# CONNECTIVITY.net
KiCad netlist of a schematic drawn in Altium Designer
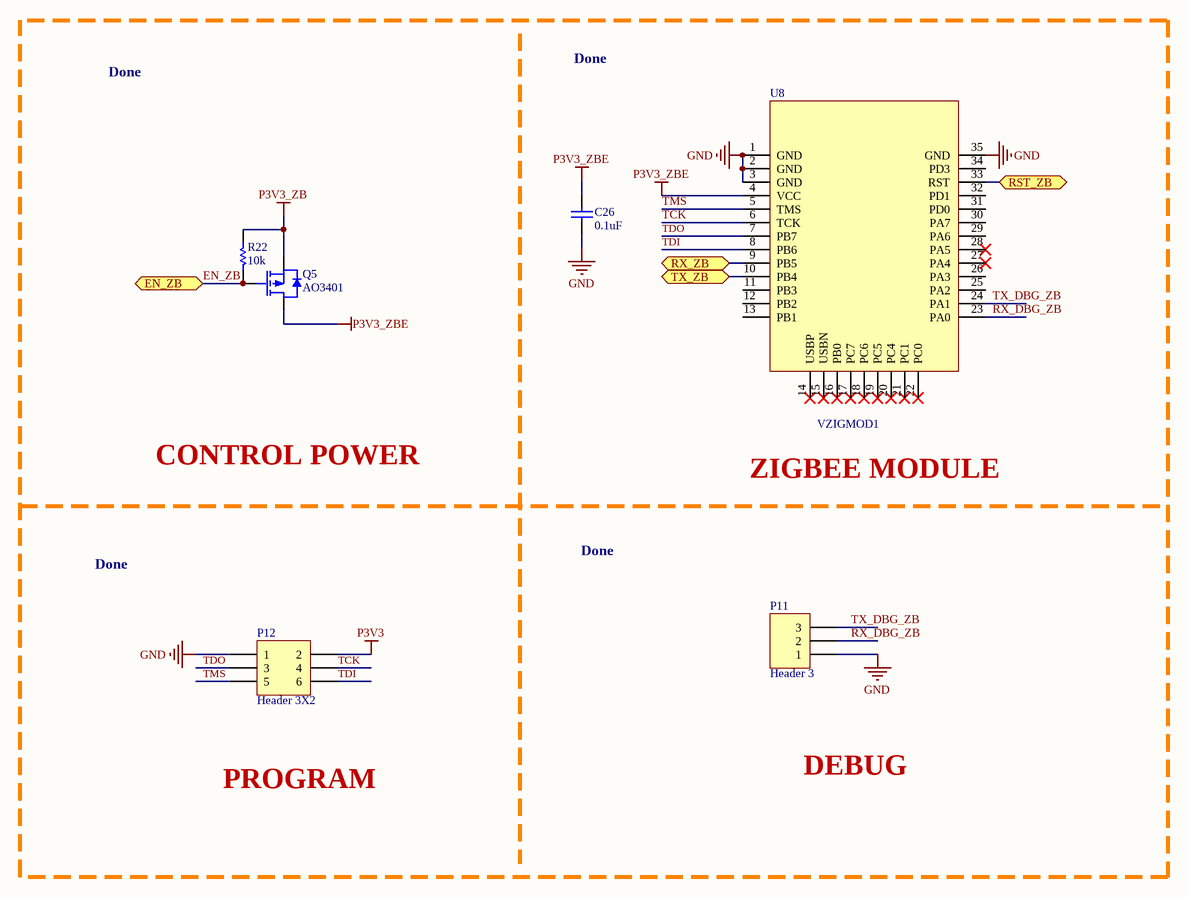
[diagram p0: CONNECTIVITY.SchDoc]

(export (version "E")
  (design (tool "Eeschema 10.0.6"))
  (components
    (comp (ref "C26")
      (value "0.1uF")
      (footprint "C0402M")
      (description "CAP CER 0.1UF 16V X7R 0402")
      (fields
        (field (name "MANUFACTURER") "Samsung Electro-Mechanics")
        (field (name "MANUFACTURER PART NUMBER") "CL05B104KO5NNNC")
      )
      (libsource (lib "BinhLib") (part "CAP0.1u0402"))
    )
    (comp (ref "P11")
      (value "Header 3")
      (footprint "HDR1X3")
      (description "Header, 3-Pin")
      (fields (field (name "PUBLISHER") "Altium Limited"))
      (libsource (lib "BinhLib") (part "Header 3"))
    )
    (comp (ref "P12")
      (value "Header 3X2")
      (footprint "HDR2X3")
      (description "Header, 3-Pin, Dual row")
      (fields (field (name "PUBLISHER") "Altium Limited"))
      (libsource (lib "BinhLib") (part "Header 3X2"))
    )
    (comp (ref "Q5")
      (value "AO3401")
      (footprint "SOT23-3N")
      (description "P-Channel MOSFET")
      (libsource (lib "BinhLib") (part "MOSFET-P1"))
    )
    (comp (ref "R22")
      (value "10k")
      (footprint "R0603M")
      (description "RES SMD 10K OHM 1% 1/10W 0603")
      (fields
        (field (name "MANUFACTURER") "Panasonic Electronic Components")
        (field (name "MANUFACTURER PART NUMBER") "ERJ-3EKF1002V")
      )
      (libsource (lib "BinhLib") (part "RES10k0603"))
    )
    (comp (ref "U8")
      (value "VZIGMOD1")
      (footprint "VZIGMOD2")
      (description "VNPT ZIGBEE MODULE V1 - No-PA")
      (fields (field (name "MANUFACTURER") "VNPT-Technology") (field (name "UTILIZED IC / PART") "CC2538"))
      (libsource (lib "SensorNode") (part "VZIGMOD2"))
    )
  )
  (nets
    (net (code "1") (name "/EN_ZB") (class "Default")
      (node (ref "Q5") (pin "1") (pinfunction "G_1") (pintype "passive"))
      (node (ref "R22") (pin "1") (pinfunction "1_1") (pintype "passive"))
    )
    (net (code "2") (name "/RST_ZB") (class "Default")
      (node (ref "U8") (pin "33") (pinfunction "RST_33") (pintype "passive"))
    )
    (net (code "3") (name "/RX_DBG_ZB") (class "Default")
      (node (ref "P11") (pin "2") (pinfunction "2_2") (pintype "passive"))
      (node (ref "U8") (pin "23") (pinfunction "PA0_23") (pintype "passive"))
    )
    (net (code "4") (name "/RX_ZB") (class "Default")
      (node (ref "U8") (pin "9") (pinfunction "PB5_9") (pintype "passive"))
    )
    (net (code "5") (name "/TCK") (class "Default")
      (node (ref "P12") (pin "4") (pinfunction "4_4") (pintype "passive"))
      (node (ref "U8") (pin "6") (pinfunction "TCK_6") (pintype "passive"))
    )
    (net (code "6") (name "/TDI") (class "Default")
      (node (ref "P12") (pin "6") (pinfunction "6_6") (pintype "passive"))
      (node (ref "U8") (pin "8") (pinfunction "PB6_8") (pintype "passive"))
    )
    (net (code "7") (name "/TDO") (class "Default")
      (node (ref "P12") (pin "3") (pinfunction "3_3") (pintype "passive"))
      (node (ref "U8") (pin "7") (pinfunction "PB7_7") (pintype "passive"))
    )
    (net (code "8") (name "/TMS") (class "Default")
      (node (ref "P12") (pin "5") (pinfunction "5_5") (pintype "passive"))
      (node (ref "U8") (pin "5") (pinfunction "TMS_5") (pintype "passive"))
    )
    (net (code "9") (name "/TX_DBG_ZB") (class "Default")
      (node (ref "P11") (pin "3") (pinfunction "3_3") (pintype "passive"))
      (node (ref "U8") (pin "24") (pinfunction "PA1_24") (pintype "passive"))
    )
    (net (code "10") (name "/TX_ZB") (class "Default")
      (node (ref "U8") (pin "10") (pinfunction "PB4_10") (pintype "passive"))
    )
    (net (code "11") (name "GND") (class "Default")
      (node (ref "C26") (pin "1") (pintype "passive"))
      (node (ref "P11") (pin "1") (pinfunction "1_1") (pintype "passive"))
      (node (ref "P12") (pin "1") (pinfunction "1_1") (pintype "passive"))
      (node (ref "U8") (pin "1") (pinfunction "GND_1") (pintype "passive"))
      (node (ref "U8") (pin "2") (pinfunction "GND_2") (pintype "passive"))
      (node (ref "U8") (pin "3") (pinfunction "GND_3") (pintype "passive"))
      (node (ref "U8") (pin "35") (pinfunction "GND_35") (pintype "passive"))
    )
    (net (code "12") (name "P3V3") (class "Default")
      (node (ref "P12") (pin "2") (pinfunction "2_2") (pintype "passive"))
    )
    (net (code "13") (name "P3V3_ZB") (class "Default")
      (node (ref "Q5") (pin "2") (pinfunction "S_2") (pintype "passive"))
      (node (ref "R22") (pin "2") (pinfunction "2_2") (pintype "passive"))
    )
    (net (code "14") (name "P3V3_ZBE") (class "Default")
      (node (ref "C26") (pin "2") (pintype "passive"))
      (node (ref "Q5") (pin "3") (pinfunction "D_3") (pintype "passive"))
      (node (ref "U8") (pin "4") (pinfunction "VCC_4") (pintype "passive"))
    )
    (net (code "15") (name "unconnected-(U8-PA2-Pad25)") (class "Default")
      (node (ref "U8") (pin "25") (pinfunction "PA2_25") (pintype "passive"))
    )
    (net (code "16") (name "unconnected-(U8-PA3-Pad26)") (class "Default")
      (node (ref "U8") (pin "26") (pinfunction "PA3_26") (pintype "passive"))
    )
    (net (code "17") (name "unconnected-(U8-PA4-Pad27)") (class "Default")
      (node (ref "U8") (pin "27") (pinfunction "PA4_27") (pintype "passive+no_connect"))
    )
    (net (code "18") (name "unconnected-(U8-PA5-Pad28)") (class "Default")
      (node (ref "U8") (pin "28") (pinfunction "PA5_28") (pintype "passive+no_connect"))
    )
    (net (code "19") (name "unconnected-(U8-PA6-Pad29)") (class "Default")
      (node (ref "U8") (pin "29") (pinfunction "PA6_29") (pintype "passive"))
    )
    (net (code "20") (name "unconnected-(U8-PA7-Pad30)") (class "Default")
      (node (ref "U8") (pin "30") (pinfunction "PA7_30") (pintype "passive"))
    )
    (net (code "21") (name "unconnected-(U8-PB0-Pad16)") (class "Default")
      (node (ref "U8") (pin "16") (pinfunction "PB0_16") (pintype "passive+no_connect"))
    )
    (net (code "22") (name "unconnected-(U8-PB1-Pad13)") (class "Default")
      (node (ref "U8") (pin "13") (pinfunction "PB1_13") (pintype "passive"))
    )
    (net (code "23") (name "unconnected-(U8-PB2-Pad12)") (class "Default")
      (node (ref "U8") (pin "12") (pinfunction "PB2_12") (pintype "passive"))
    )
    (net (code "24") (name "unconnected-(U8-PB3-Pad11)") (class "Default")
      (node (ref "U8") (pin "11") (pinfunction "PB3_11") (pintype "passive"))
    )
    (net (code "25") (name "unconnected-(U8-PC0-Pad22)") (class "Default")
      (node (ref "U8") (pin "22") (pinfunction "PC0_22") (pintype "passive+no_connect"))
    )
    (net (code "26") (name "unconnected-(U8-PC1-Pad21)") (class "Default")
      (node (ref "U8") (pin "21") (pinfunction "PC1_21") (pintype "passive+no_connect"))
    )
    (net (code "27") (name "unconnected-(U8-PC4-Pad20)") (class "Default")
      (node (ref "U8") (pin "20") (pinfunction "PC4_20") (pintype "passive+no_connect"))
    )
    (net (code "28") (name "unconnected-(U8-PC5-Pad19)") (class "Default")
      (node (ref "U8") (pin "19") (pinfunction "PC5_19") (pintype "passive+no_connect"))
    )
    (net (code "29") (name "unconnected-(U8-PC6-Pad18)") (class "Default")
      (node (ref "U8") (pin "18") (pinfunction "PC6_18") (pintype "passive+no_connect"))
    )
    (net (code "30") (name "unconnected-(U8-PC7-Pad17)") (class "Default")
      (node (ref "U8") (pin "17") (pinfunction "PC7_17") (pintype "passive+no_connect"))
    )
    (net (code "31") (name "unconnected-(U8-PD0-Pad31)") (class "Default")
      (node (ref "U8") (pin "31") (pinfunction "PD0_31") (pintype "passive"))
    )
    (net (code "32") (name "unconnected-(U8-PD1-Pad32)") (class "Default")
      (node (ref "U8") (pin "32") (pinfunction "PD1_32") (pintype "passive"))
    )
    (net (code "33") (name "unconnected-(U8-PD3-Pad34)") (class "Default")
      (node (ref "U8") (pin "34") (pinfunction "PD3_34") (pintype "passive"))
    )
    (net (code "34") (name "unconnected-(U8-USBN-Pad15)") (class "Default")
      (node (ref "U8") (pin "15") (pinfunction "USBN_15") (pintype "passive+no_connect"))
    )
    (net (code "35") (name "unconnected-(U8-USBP-Pad14)") (class "Default")
      (node (ref "U8") (pin "14") (pinfunction "USBP_14") (pintype "passive+no_connect"))
    )
  )
)
